# polargraph.net
KiCad netlist of a schematic drawn in EAGLE
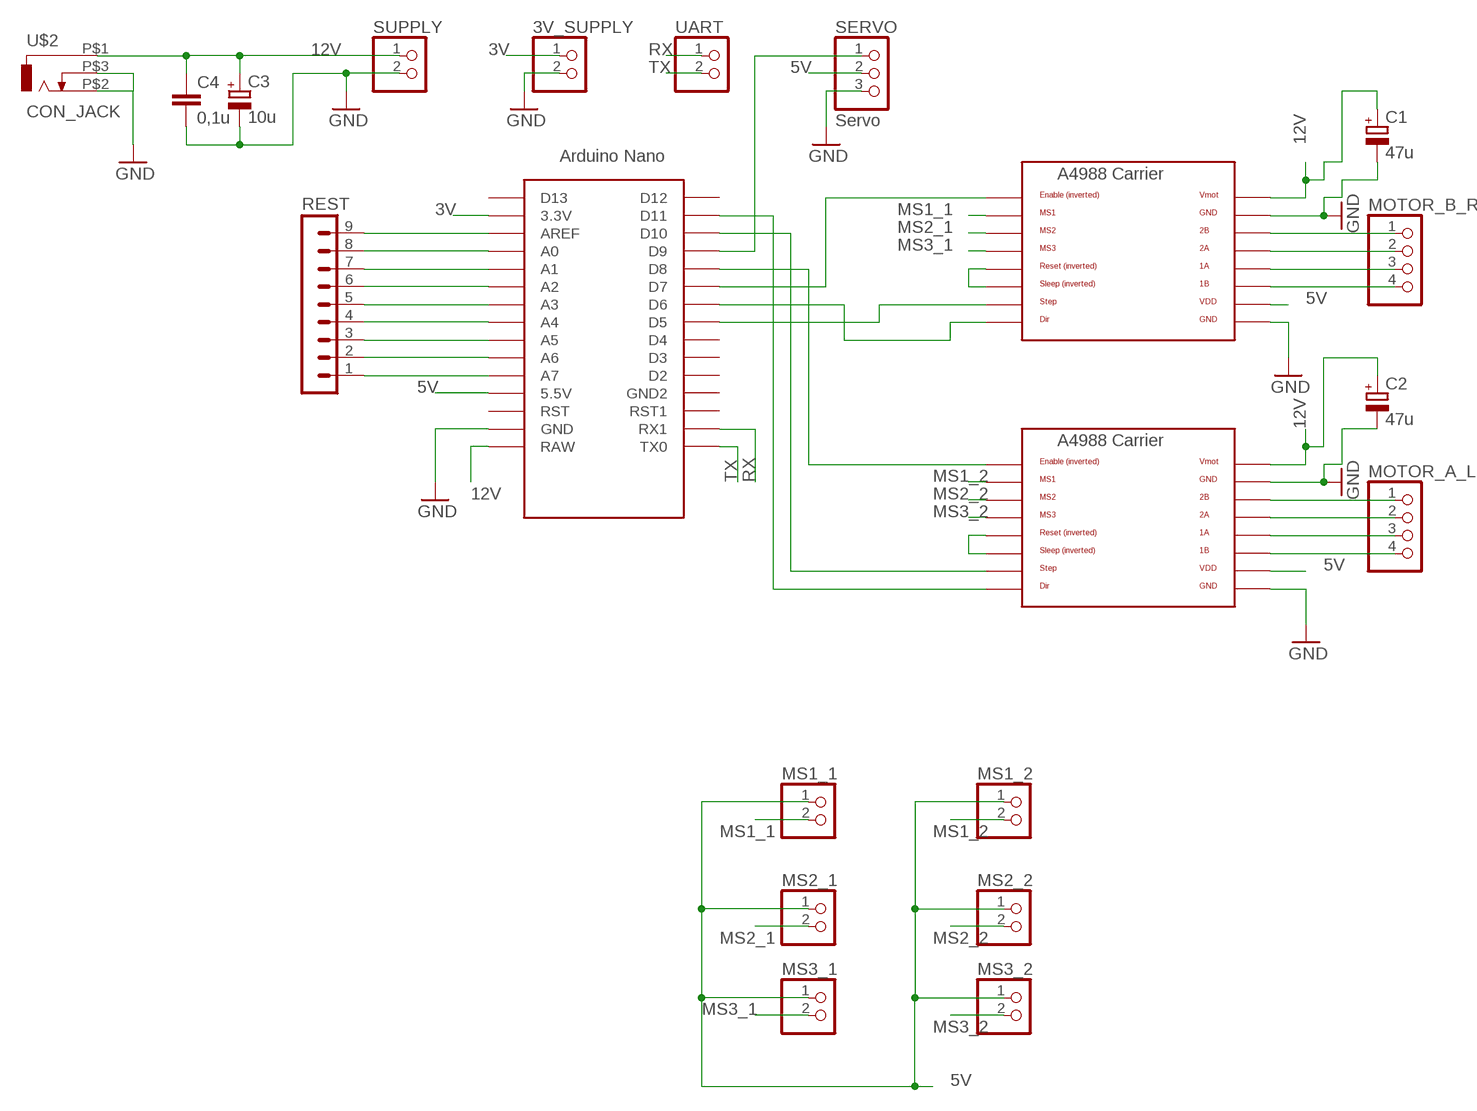
[diagram p0: schematic, sheet 1]

(export (version "E")
  (design (tool "Eeschema 10.0.6"))
  (components
    (comp (ref "3V_SUPPLY")
      (value "PINHD-1X2")
      (footprint "eagle-import:1X02")
      (libsource (lib "eagle-import") (part "PINHD-1X2"))
    )
    (comp (ref "C1")
      (value "47u")
      (footprint "eagle-import:E3,5-10")
      (libsource (lib "eagle-import") (part "CPOL-EUE3.5-10"))
    )
    (comp (ref "C2")
      (value "47u")
      (footprint "eagle-import:E3,5-10")
      (libsource (lib "eagle-import") (part "CPOL-EUE3.5-10"))
    )
    (comp (ref "C3")
      (value "10u")
      (footprint "eagle-import:E3,5-10")
      (libsource (lib "eagle-import") (part "CPOL-EUE3.5-10"))
    )
    (comp (ref "C4")
      (value "0,1u")
      (footprint "eagle-import:C0805")
      (libsource (lib "eagle-import") (part "C-EUC0805"))
    )
    (comp (ref "DRIVER_LEFT")
      (value "A4988BREAKOUT")
      (footprint "eagle-import:A4988BREAKOUT")
      (libsource (lib "eagle-import") (part "A4988BREAKOUT"))
    )
    (comp (ref "DRIVER_R")
      (value "A4988BREAKOUT")
      (footprint "eagle-import:A4988BREAKOUT")
      (libsource (lib "eagle-import") (part "A4988BREAKOUT"))
    )
    (comp (ref "MOTOR_A_L")
      (value "PINHD-1X4")
      (footprint "eagle-import:1X04")
      (libsource (lib "eagle-import") (part "PINHD-1X4"))
    )
    (comp (ref "MOTOR_B_R")
      (value "PINHD-1X4")
      (footprint "eagle-import:1X04")
      (libsource (lib "eagle-import") (part "PINHD-1X4"))
    )
    (comp (ref "MS1_1")
      (value "PINHD-1X2")
      (footprint "eagle-import:1X02")
      (libsource (lib "eagle-import") (part "PINHD-1X2"))
    )
    (comp (ref "MS1_2")
      (value "PINHD-1X2")
      (footprint "eagle-import:1X02")
      (libsource (lib "eagle-import") (part "PINHD-1X2"))
    )
    (comp (ref "MS2_1")
      (value "PINHD-1X2")
      (footprint "eagle-import:1X02")
      (libsource (lib "eagle-import") (part "PINHD-1X2"))
    )
    (comp (ref "MS2_2")
      (value "PINHD-1X2")
      (footprint "eagle-import:1X02")
      (libsource (lib "eagle-import") (part "PINHD-1X2"))
    )
    (comp (ref "MS3_1")
      (value "PINHD-1X2")
      (footprint "eagle-import:1X02")
      (libsource (lib "eagle-import") (part "PINHD-1X2"))
    )
    (comp (ref "MS3_2")
      (value "PINHD-1X2")
      (footprint "eagle-import:1X02")
      (libsource (lib "eagle-import") (part "PINHD-1X2"))
    )
    (comp (ref "REST")
      (value "MA09-1")
      (footprint "eagle-import:MA09-1")
      (libsource (lib "eagle-import") (part "MA09-1"))
    )
    (comp (ref "SERVO")
      (value "Servo")
      (footprint "eagle-import:1X03")
      (libsource (lib "eagle-import") (part "PINHD-1X3"))
    )
    (comp (ref "SUPPLY")
      (value "PINHD-1X2")
      (footprint "eagle-import:1X02")
      (libsource (lib "eagle-import") (part "PINHD-1X2"))
    )
    (comp (ref "U$1")
      (value "NANO")
      (footprint "eagle-import:NANO")
      (libsource (lib "eagle-import") (part "NANO"))
    )
    (comp (ref "U$2")
      (value "CON_JACK")
      (footprint "eagle-import:CON_JACK")
      (libsource (lib "eagle-import") (part "CON_JACK"))
    )
    (comp (ref "UART")
      (value "PINHD-1X2")
      (footprint "eagle-import:1X02")
      (libsource (lib "eagle-import") (part "PINHD-1X2"))
    )
  )
  (nets
    (net (code "1") (name "/3V") (class "Default")
      (node (ref "3V_SUPPLY") (pin "1") (pinfunction "1_1") (pintype "passive"))
      (node (ref "U$1") (pin "3.3V") (pinfunction "3.3V_3.3V") (pintype "bidirectional"))
    )
    (net (code "2") (name "/5V") (class "Default")
      (node (ref "DRIVER_LEFT") (pin "VDD") (pinfunction "VDD_VDD") (pintype "power_in"))
      (node (ref "DRIVER_R") (pin "VDD") (pinfunction "VDD_VDD") (pintype "power_in"))
      (node (ref "MS1_1") (pin "1") (pinfunction "1_1") (pintype "passive"))
      (node (ref "MS1_2") (pin "1") (pinfunction "1_1") (pintype "passive"))
      (node (ref "MS2_1") (pin "1") (pinfunction "1_1") (pintype "passive"))
      (node (ref "MS2_2") (pin "1") (pinfunction "1_1") (pintype "passive"))
      (node (ref "MS3_1") (pin "1") (pinfunction "1_1") (pintype "passive"))
      (node (ref "MS3_2") (pin "1") (pinfunction "1_1") (pintype "passive"))
      (node (ref "SERVO") (pin "2") (pinfunction "2_2") (pintype "passive"))
      (node (ref "U$1") (pin "5V") (pinfunction "5.5V_5V") (pintype "bidirectional"))
    )
    (net (code "3") (name "/12V") (class "Default")
      (node (ref "C1") (pin "+") (pinfunction "+_+") (pintype "passive"))
      (node (ref "C2") (pin "+") (pinfunction "+_+") (pintype "passive"))
      (node (ref "C3") (pin "+") (pinfunction "+_+") (pintype "passive"))
      (node (ref "C4") (pin "1") (pinfunction "1_1") (pintype "passive"))
      (node (ref "DRIVER_LEFT") (pin "VMOT") (pinfunction "VMOT_VMOT") (pintype "power_in"))
      (node (ref "DRIVER_R") (pin "VMOT") (pinfunction "VMOT_VMOT") (pintype "power_in"))
      (node (ref "SUPPLY") (pin "1") (pinfunction "1_1") (pintype "passive"))
      (node (ref "U$1") (pin "RAW") (pinfunction "RAW_RAW") (pintype "bidirectional"))
      (node (ref "U$2") (pin "P$1") (pinfunction "V1_P$1") (pintype "passive"))
    )
    (net (code "4") (name "/MS1_1") (class "Default")
      (node (ref "DRIVER_R") (pin "MS1") (pinfunction "MS1_MS1") (pintype "input"))
      (node (ref "MS1_1") (pin "2") (pinfunction "2_2") (pintype "passive"))
    )
    (net (code "5") (name "/MS1_2") (class "Default")
      (node (ref "DRIVER_LEFT") (pin "MS1") (pinfunction "MS1_MS1") (pintype "input"))
      (node (ref "MS1_2") (pin "2") (pinfunction "2_2") (pintype "passive"))
    )
    (net (code "6") (name "/MS2_1") (class "Default")
      (node (ref "DRIVER_R") (pin "MS2") (pinfunction "MS2_MS2") (pintype "input"))
      (node (ref "MS2_1") (pin "2") (pinfunction "2_2") (pintype "passive"))
    )
    (net (code "7") (name "/MS2_2") (class "Default")
      (node (ref "DRIVER_LEFT") (pin "MS2") (pinfunction "MS2_MS2") (pintype "input"))
      (node (ref "MS2_2") (pin "2") (pinfunction "2_2") (pintype "passive"))
    )
    (net (code "8") (name "/MS3_1") (class "Default")
      (node (ref "DRIVER_R") (pin "MS3") (pinfunction "MS3_MS3") (pintype "input"))
      (node (ref "MS3_1") (pin "2") (pinfunction "2_2") (pintype "passive"))
    )
    (net (code "9") (name "/MS3_2") (class "Default")
      (node (ref "DRIVER_LEFT") (pin "MS3") (pinfunction "MS3_MS3") (pintype "input"))
      (node (ref "MS3_2") (pin "2") (pinfunction "2_2") (pintype "passive"))
    )
    (net (code "10") (name "/RX") (class "Default")
      (node (ref "U$1") (pin "RX1") (pinfunction "RX1_RX1") (pintype "bidirectional"))
      (node (ref "UART") (pin "1") (pinfunction "1_1") (pintype "passive"))
    )
    (net (code "11") (name "/TX") (class "Default")
      (node (ref "U$1") (pin "TX0") (pinfunction "TX0_TX0") (pintype "bidirectional"))
      (node (ref "UART") (pin "2") (pinfunction "2_2") (pintype "passive"))
    )
    (net (code "12") (name "GND") (class "Default")
      (node (ref "3V_SUPPLY") (pin "2") (pinfunction "2_2") (pintype "passive"))
      (node (ref "C1") (pin "-") (pinfunction "-_-") (pintype "passive"))
      (node (ref "C2") (pin "-") (pinfunction "-_-") (pintype "passive"))
      (node (ref "C3") (pin "-") (pinfunction "-_-") (pintype "passive"))
      (node (ref "C4") (pin "2") (pinfunction "2_2") (pintype "passive"))
      (node (ref "DRIVER_LEFT") (pin "GND") (pinfunction "GND_GND") (pintype "power_in"))
      (node (ref "DRIVER_LEFT") (pin "GND@0") (pinfunction "GND_GND@0") (pintype "power_in"))
      (node (ref "DRIVER_R") (pin "GND") (pinfunction "GND_GND") (pintype "power_in"))
      (node (ref "DRIVER_R") (pin "GND@0") (pinfunction "GND_GND@0") (pintype "power_in"))
      (node (ref "SERVO") (pin "3") (pinfunction "3_3") (pintype "passive"))
      (node (ref "SUPPLY") (pin "2") (pinfunction "2_2") (pintype "passive"))
      (node (ref "U$1") (pin "GND") (pinfunction "GND_GND") (pintype "bidirectional"))
      (node (ref "U$2") (pin "P$2") (pinfunction "G3_P$2") (pintype "passive"))
      (node (ref "U$2") (pin "P$3") (pinfunction "G2_P$3") (pintype "passive"))
    )
    (net (code "13") (name "Net-(DRIVER_LEFT-Pad1A)") (class "Default")
      (node (ref "DRIVER_LEFT") (pin "1A") (pinfunction "1A_1A") (pintype "output"))
      (node (ref "MOTOR_A_L") (pin "3") (pinfunction "3_3") (pintype "passive"))
    )
    (net (code "14") (name "Net-(DRIVER_LEFT-Pad1B)") (class "Default")
      (node (ref "DRIVER_LEFT") (pin "1B") (pinfunction "1B_1B") (pintype "output"))
      (node (ref "MOTOR_A_L") (pin "4") (pinfunction "4_4") (pintype "passive"))
    )
    (net (code "15") (name "Net-(DRIVER_LEFT-Pad2A)") (class "Default")
      (node (ref "DRIVER_LEFT") (pin "2A") (pinfunction "2A_2A") (pintype "output"))
      (node (ref "MOTOR_A_L") (pin "2") (pinfunction "2_2") (pintype "passive"))
    )
    (net (code "16") (name "Net-(DRIVER_LEFT-Pad2B)") (class "Default")
      (node (ref "DRIVER_LEFT") (pin "2B") (pinfunction "2B_2B") (pintype "output"))
      (node (ref "MOTOR_A_L") (pin "1") (pinfunction "1_1") (pintype "passive"))
    )
    (net (code "17") (name "Net-(DRIVER_LEFT-PadDIR)") (class "Default")
      (node (ref "DRIVER_LEFT") (pin "DIR") (pinfunction "DIR_DIR") (pintype "input"))
      (node (ref "U$1") (pin "D11") (pinfunction "D11_D11") (pintype "bidirectional"))
    )
    (net (code "18") (name "Net-(DRIVER_LEFT-PadEN)") (class "Default")
      (node (ref "DRIVER_LEFT") (pin "EN") (pinfunction "EN_EN") (pintype "input"))
      (node (ref "U$1") (pin "D8") (pinfunction "D8_D8") (pintype "bidirectional"))
    )
    (net (code "19") (name "Net-(DRIVER_LEFT-PadSTEP)") (class "Default")
      (node (ref "DRIVER_LEFT") (pin "STEP") (pinfunction "STEP_STEP") (pintype "input"))
      (node (ref "U$1") (pin "D10") (pinfunction "D10_D10") (pintype "bidirectional"))
    )
    (net (code "20") (name "Net-(DRIVER_LEFT-SLEEP)") (class "Default")
      (node (ref "DRIVER_LEFT") (pin "RST") (pinfunction "RST_RST") (pintype "input"))
      (node (ref "DRIVER_LEFT") (pin "SLP") (pinfunction "SLEEP_SLP") (pintype "input"))
    )
    (net (code "21") (name "Net-(DRIVER_R-Pad1A)") (class "Default")
      (node (ref "DRIVER_R") (pin "1A") (pinfunction "1A_1A") (pintype "output"))
      (node (ref "MOTOR_B_R") (pin "3") (pinfunction "3_3") (pintype "passive"))
    )
    (net (code "22") (name "Net-(DRIVER_R-Pad1B)") (class "Default")
      (node (ref "DRIVER_R") (pin "1B") (pinfunction "1B_1B") (pintype "output"))
      (node (ref "MOTOR_B_R") (pin "4") (pinfunction "4_4") (pintype "passive"))
    )
    (net (code "23") (name "Net-(DRIVER_R-Pad2A)") (class "Default")
      (node (ref "DRIVER_R") (pin "2A") (pinfunction "2A_2A") (pintype "output"))
      (node (ref "MOTOR_B_R") (pin "2") (pinfunction "2_2") (pintype "passive"))
    )
    (net (code "24") (name "Net-(DRIVER_R-Pad2B)") (class "Default")
      (node (ref "DRIVER_R") (pin "2B") (pinfunction "2B_2B") (pintype "output"))
      (node (ref "MOTOR_B_R") (pin "1") (pinfunction "1_1") (pintype "passive"))
    )
    (net (code "25") (name "Net-(DRIVER_R-PadDIR)") (class "Default")
      (node (ref "DRIVER_R") (pin "DIR") (pinfunction "DIR_DIR") (pintype "input"))
      (node (ref "U$1") (pin "D6") (pinfunction "D6_D6") (pintype "bidirectional"))
    )
    (net (code "26") (name "Net-(DRIVER_R-PadEN)") (class "Default")
      (node (ref "DRIVER_R") (pin "EN") (pinfunction "EN_EN") (pintype "input"))
      (node (ref "U$1") (pin "D7") (pinfunction "D7_D7") (pintype "bidirectional"))
    )
    (net (code "27") (name "Net-(DRIVER_R-PadSTEP)") (class "Default")
      (node (ref "DRIVER_R") (pin "STEP") (pinfunction "STEP_STEP") (pintype "input"))
      (node (ref "U$1") (pin "D5") (pinfunction "D5_D5") (pintype "bidirectional"))
    )
    (net (code "28") (name "Net-(DRIVER_R-SLEEP)") (class "Default")
      (node (ref "DRIVER_R") (pin "RST") (pinfunction "RST_RST") (pintype "input"))
      (node (ref "DRIVER_R") (pin "SLP") (pinfunction "SLEEP_SLP") (pintype "input"))
    )
    (net (code "29") (name "Net-(REST-Pad1)") (class "Default")
      (node (ref "REST") (pin "1") (pinfunction "1_1") (pintype "passive"))
      (node (ref "U$1") (pin "A7") (pinfunction "A7_A7") (pintype "bidirectional"))
    )
    (net (code "30") (name "Net-(REST-Pad2)") (class "Default")
      (node (ref "REST") (pin "2") (pinfunction "2_2") (pintype "passive"))
      (node (ref "U$1") (pin "A6") (pinfunction "A6_A6") (pintype "bidirectional"))
    )
    (net (code "31") (name "Net-(REST-Pad3)") (class "Default")
      (node (ref "REST") (pin "3") (pinfunction "3_3") (pintype "passive"))
      (node (ref "U$1") (pin "A5") (pinfunction "A5_A5") (pintype "bidirectional"))
    )
    (net (code "32") (name "Net-(REST-Pad4)") (class "Default")
      (node (ref "REST") (pin "4") (pinfunction "4_4") (pintype "passive"))
      (node (ref "U$1") (pin "A4") (pinfunction "A4_A4") (pintype "bidirectional"))
    )
    (net (code "33") (name "Net-(REST-Pad5)") (class "Default")
      (node (ref "REST") (pin "5") (pinfunction "5_5") (pintype "passive"))
      (node (ref "U$1") (pin "A3") (pinfunction "A3_A3") (pintype "bidirectional"))
    )
    (net (code "34") (name "Net-(REST-Pad6)") (class "Default")
      (node (ref "REST") (pin "6") (pinfunction "6_6") (pintype "passive"))
      (node (ref "U$1") (pin "A2") (pinfunction "A2_A2") (pintype "bidirectional"))
    )
    (net (code "35") (name "Net-(REST-Pad7)") (class "Default")
      (node (ref "REST") (pin "7") (pinfunction "7_7") (pintype "passive"))
      (node (ref "U$1") (pin "A1") (pinfunction "A1_A1") (pintype "bidirectional"))
    )
    (net (code "36") (name "Net-(REST-Pad8)") (class "Default")
      (node (ref "REST") (pin "8") (pinfunction "8_8") (pintype "passive"))
      (node (ref "U$1") (pin "A0") (pinfunction "A0_A0") (pintype "bidirectional"))
    )
    (net (code "37") (name "Net-(REST-Pad9)") (class "Default")
      (node (ref "REST") (pin "9") (pinfunction "9_9") (pintype "passive"))
      (node (ref "U$1") (pin "AREF") (pinfunction "AREF_AREF") (pintype "bidirectional"))
    )
    (net (code "38") (name "Net-(SERVO-Pad1)") (class "Default")
      (node (ref "SERVO") (pin "1") (pinfunction "1_1") (pintype "passive"))
      (node (ref "U$1") (pin "D9") (pinfunction "D9_D9") (pintype "bidirectional"))
    )
    (net (code "39") (name "unconnected-(U$1-GND2-PadGND1)") (class "Default")
      (node (ref "U$1") (pin "GND1") (pinfunction "GND2_GND1") (pintype "bidirectional"))
    )
    (net (code "40") (name "unconnected-(U$1-PadD2)") (class "Default")
      (node (ref "U$1") (pin "D2") (pinfunction "D2_D2") (pintype "bidirectional"))
    )
    (net (code "41") (name "unconnected-(U$1-PadD3)") (class "Default")
      (node (ref "U$1") (pin "D3") (pinfunction "D3_D3") (pintype "bidirectional"))
    )
    (net (code "42") (name "unconnected-(U$1-PadD4)") (class "Default")
      (node (ref "U$1") (pin "D4") (pinfunction "D4_D4") (pintype "bidirectional"))
    )
    (net (code "43") (name "unconnected-(U$1-PadD12)") (class "Default")
      (node (ref "U$1") (pin "D12") (pinfunction "D12_D12") (pintype "bidirectional"))
    )
    (net (code "44") (name "unconnected-(U$1-PadD13)") (class "Default")
      (node (ref "U$1") (pin "D13") (pinfunction "D13_D13") (pintype "bidirectional"))
    )
    (net (code "45") (name "unconnected-(U$1-PadICSP1)") (class "Default")
      (node (ref "U$1") (pin "ICSP1") (pinfunction "ICSP1_ICSP1") (pintype "bidirectional"))
    )
    (net (code "46") (name "unconnected-(U$1-PadICSP2)") (class "Default")
      (node (ref "U$1") (pin "ICSP2") (pinfunction "ICSP2_ICSP2") (pintype "bidirectional"))
    )
    (net (code "47") (name "unconnected-(U$1-PadICSP3)") (class "Default")
      (node (ref "U$1") (pin "ICSP3") (pinfunction "ICSP3_ICSP3") (pintype "bidirectional"))
    )
    (net (code "48") (name "unconnected-(U$1-PadICSP4)") (class "Default")
      (node (ref "U$1") (pin "ICSP4") (pinfunction "ICSP4_ICSP4") (pintype "bidirectional"))
    )
    (net (code "49") (name "unconnected-(U$1-PadICSP5)") (class "Default")
      (node (ref "U$1") (pin "ICSP5") (pinfunction "ICSP5_ICSP5") (pintype "bidirectional"))
    )
    (net (code "50") (name "unconnected-(U$1-PadICSP6)") (class "Default")
      (node (ref "U$1") (pin "ICSP6") (pinfunction "ICSP6_ICSP6") (pintype "bidirectional"))
    )
    (net (code "51") (name "unconnected-(U$1-PadRST)") (class "Default")
      (node (ref "U$1") (pin "RST") (pinfunction "RST_RST") (pintype "bidirectional"))
    )
    (net (code "52") (name "unconnected-(U$1-PadRST1)") (class "Default")
      (node (ref "U$1") (pin "RST1") (pinfunction "RST1_RST1") (pintype "bidirectional"))
    )
  )
)
